# UKU207xx_power_board.net
KiCad netlist of a schematic drawn in Altium Designer
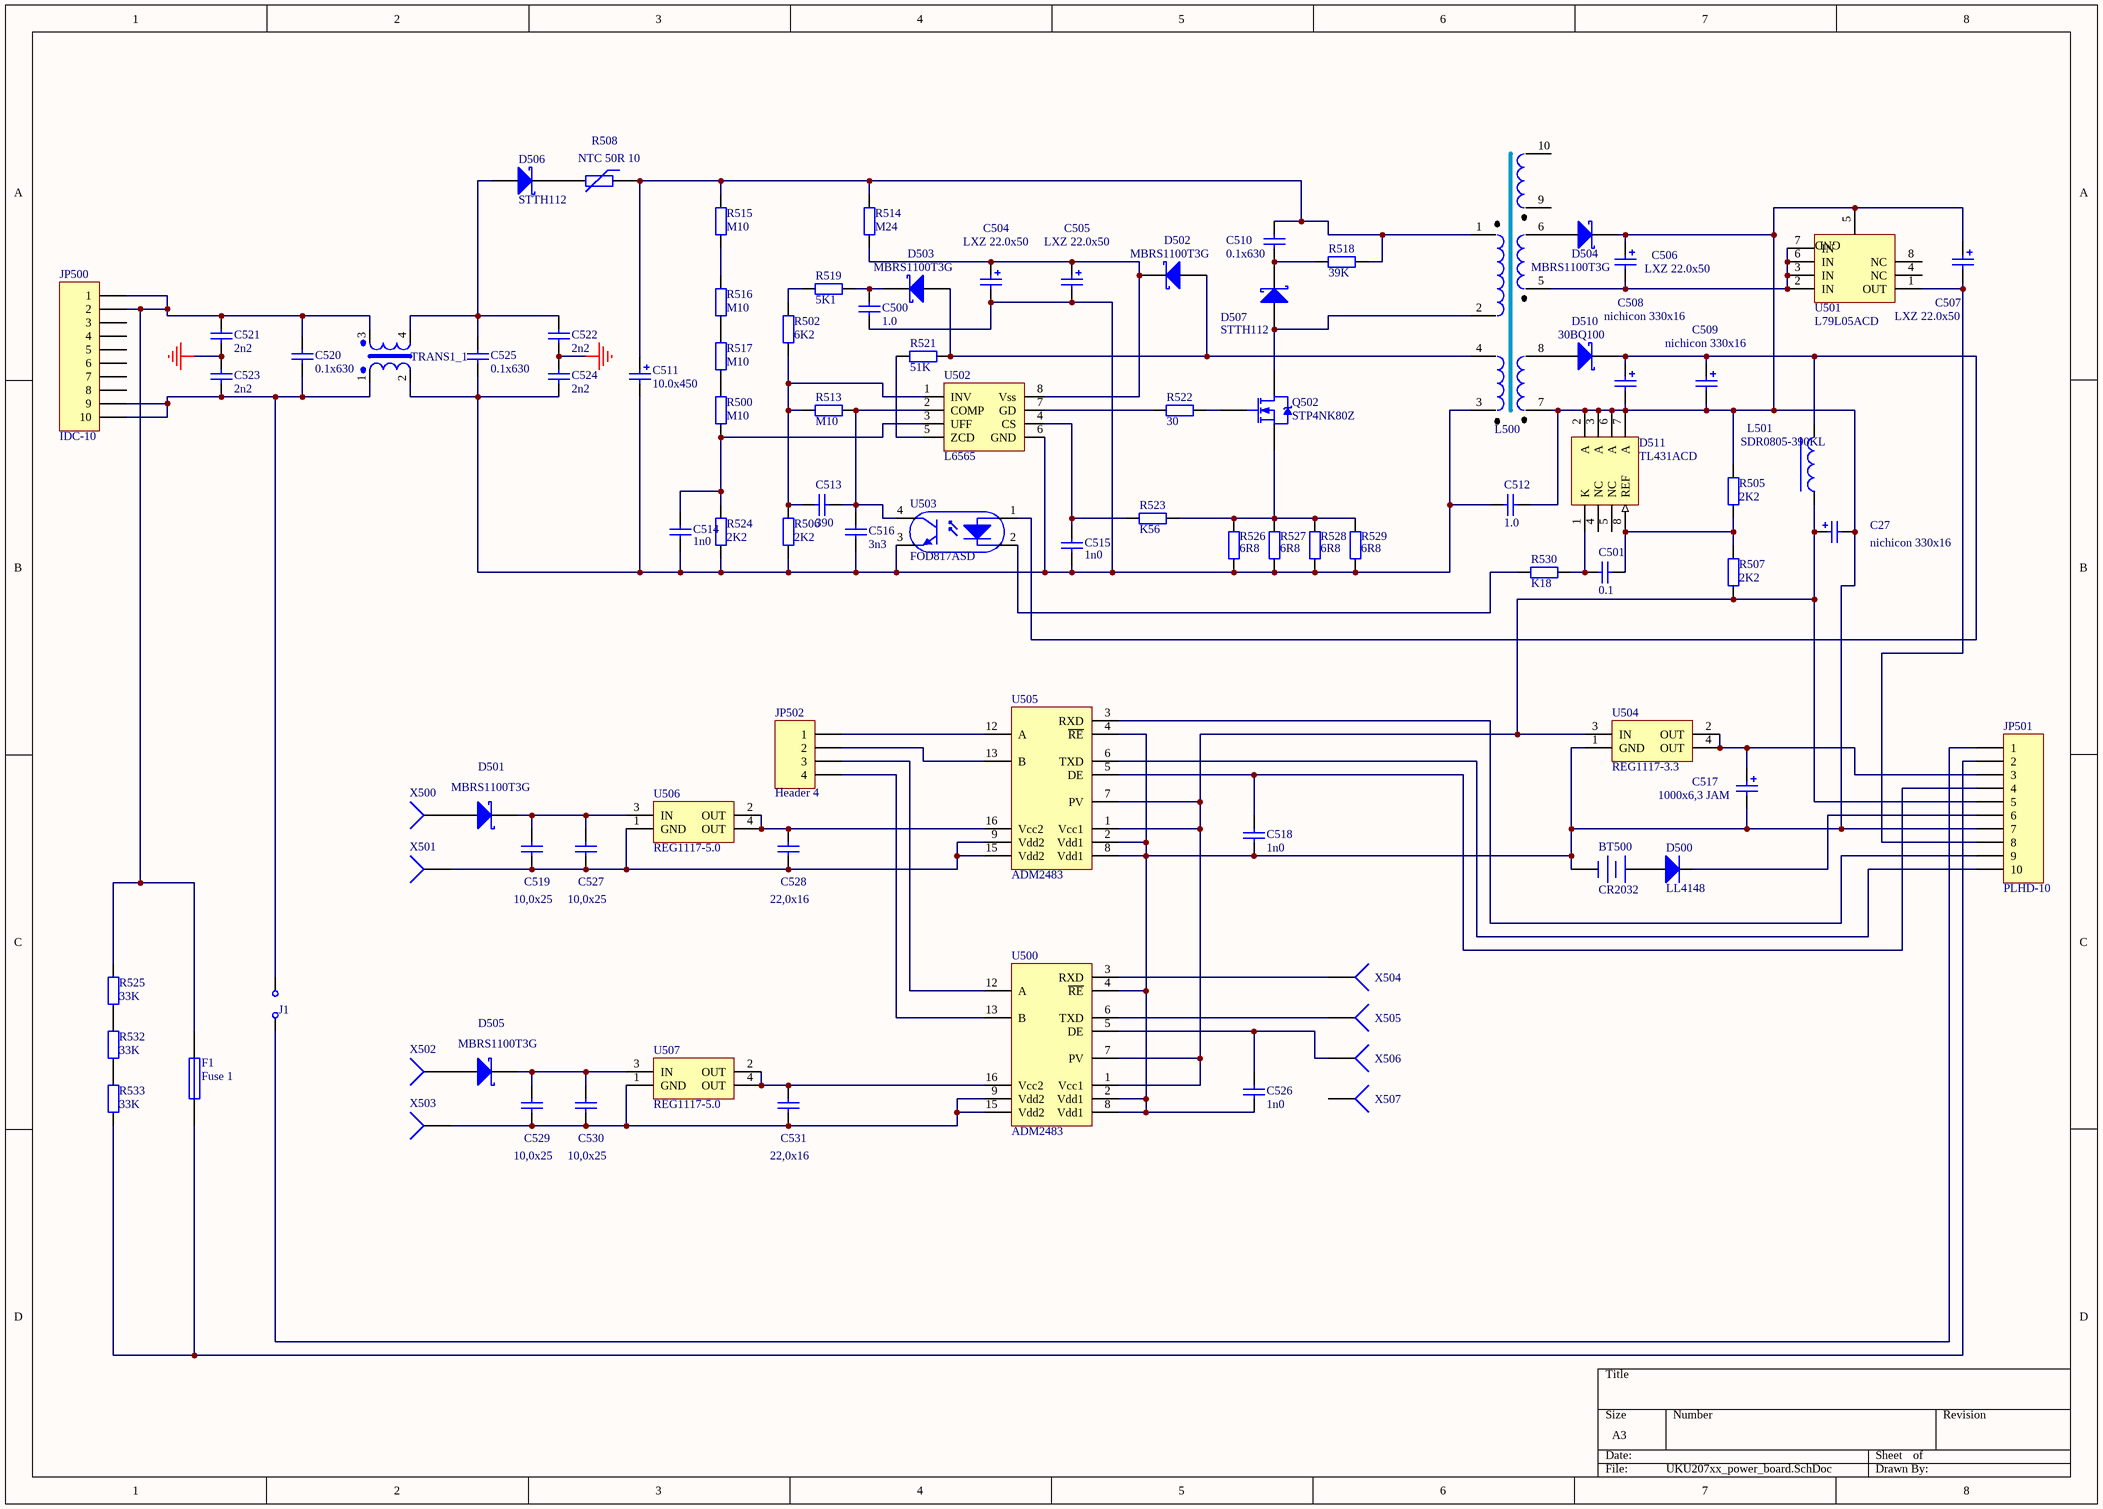
[diagram p0: UKU207xx_power_board.SchDoc]

(export (version "E")
  (design (tool "Eeschema 10.0.6"))
  (components
    (comp (ref "BT500")
      (value "CR2032")
      (footprint "BAT_HOLD_SMD")
      (description "Multicell Battery")
      (fields (field (name "MANUFACTURER") "Generic Components") (field (name "PUBLISHER") "Altium Limited"))
      (libsource (lib "Miscellaneous Devices") (part "Battery"))
    )
    (comp (ref "C27")
      (value "nichicon 330x16")
      (footprint "el3")
      (description "Polarized Capacitor (Radial)")
      (fields (field (name "MANUFACTURER") "Generic Components") (field (name "PUBLISHER") "Altium Limited"))
      (libsource (lib "PAL") (part "Cap Pol1"))
    )
    (comp (ref "C500")
      (value "1.0")
      (footprint "_1206")
      (description "Capacitor (Semiconductor SIM Model)")
      (fields (field (name "MANUFACTURER") "Generic Components") (field (name "PUBLISHER") "Altium Limited"))
      (libsource (lib "Miscellaneous Devices") (part "Cap Semi"))
    )
    (comp (ref "C501")
      (value "0.1")
      (footprint "_1206")
      (description "Capacitor (Semiconductor SIM Model)")
      (fields (field (name "MANUFACTURER") "Generic Components") (field (name "PUBLISHER") "Altium Limited"))
      (libsource (lib "Miscellaneous Devices") (part "Cap Semi"))
    )
    (comp (ref "C504")
      (value "LXZ 22.0x50")
      (footprint "el3")
      (description "Polarized Capacitor (Radial)")
      (fields (field (name "MANUFACTURER") "Generic Components") (field (name "PUBLISHER") "Altium Limited"))
      (libsource (lib "PAL") (part "Cap Pol1"))
    )
    (comp (ref "C505")
      (value "LXZ 22.0x50")
      (footprint "el3")
      (description "Polarized Capacitor (Radial)")
      (fields (field (name "MANUFACTURER") "Generic Components") (field (name "PUBLISHER") "Altium Limited"))
      (libsource (lib "PAL") (part "Cap Pol1"))
    )
    (comp (ref "C506")
      (value "LXZ 22.0x50")
      (footprint "el3")
      (description "Polarized Capacitor (Radial)")
      (fields (field (name "MANUFACTURER") "Generic Components") (field (name "PUBLISHER") "Altium Limited"))
      (libsource (lib "PAL") (part "Cap Pol1"))
    )
    (comp (ref "C507")
      (value "LXZ 22.0x50")
      (footprint "el3")
      (description "Polarized Capacitor (Radial)")
      (fields (field (name "MANUFACTURER") "Generic Components") (field (name "PUBLISHER") "Altium Limited"))
      (libsource (lib "PAL") (part "Cap Pol1"))
    )
    (comp (ref "C508")
      (value "nichicon 330x16")
      (footprint "el3")
      (description "Polarized Capacitor (Radial)")
      (fields (field (name "MANUFACTURER") "Generic Components") (field (name "PUBLISHER") "Altium Limited"))
      (libsource (lib "PAL") (part "Cap Pol1"))
    )
    (comp (ref "C509")
      (value "nichicon 330x16")
      (footprint "el3")
      (description "Polarized Capacitor (Radial)")
      (fields (field (name "MANUFACTURER") "Generic Components") (field (name "PUBLISHER") "Altium Limited"))
      (libsource (lib "PAL") (part "Cap Pol1"))
    )
    (comp (ref "C510")
      (value "0.1x630")
      (footprint "c15")
      (description "Capacitor (Semiconductor SIM Model)")
      (fields (field (name "MANUFACTURER") "Generic Components") (field (name "PUBLISHER") "Altium Limited"))
      (libsource (lib "Miscellaneous Devices") (part "Cap Semi"))
    )
    (comp (ref "C511")
      (value "10.0x450")
      (footprint "el_15_25_h")
      (description "Polarized Capacitor (Radial)")
      (fields (field (name "MANUFACTURER") "Generic Components") (field (name "PUBLISHER") "Altium Limited"))
      (libsource (lib "PAL") (part "Cap Pol1"))
    )
    (comp (ref "C512")
      (value "1.0")
      (footprint "C8")
      (description "Capacitor (Semiconductor SIM Model)")
      (fields (field (name "MANUFACTURER") "Generic Components") (field (name "PUBLISHER") "Altium Limited"))
      (libsource (lib "Miscellaneous Devices") (part "Cap Semi"))
    )
    (comp (ref "C513")
      (value "390")
      (footprint "_1206")
      (description "Capacitor (Semiconductor SIM Model)")
      (fields (field (name "MANUFACTURER") "Generic Components") (field (name "PUBLISHER") "Altium Limited"))
      (libsource (lib "Miscellaneous Devices") (part "Cap Semi"))
    )
    (comp (ref "C514")
      (value "1n0")
      (footprint "_1206")
      (description "Capacitor (Semiconductor SIM Model)")
      (fields (field (name "MANUFACTURER") "Generic Components") (field (name "PUBLISHER") "Altium Limited"))
      (libsource (lib "Miscellaneous Devices") (part "Cap Semi"))
    )
    (comp (ref "C515")
      (value "1n0")
      (footprint "_1206")
      (description "Capacitor (Semiconductor SIM Model)")
      (fields (field (name "MANUFACTURER") "Generic Components") (field (name "PUBLISHER") "Altium Limited"))
      (libsource (lib "Miscellaneous Devices") (part "Cap Semi"))
    )
    (comp (ref "C516")
      (value "3n3")
      (footprint "_1206")
      (description "Capacitor (Semiconductor SIM Model)")
      (fields (field (name "MANUFACTURER") "Generic Components") (field (name "PUBLISHER") "Altium Limited"))
      (libsource (lib "Miscellaneous Devices") (part "Cap Semi"))
    )
    (comp (ref "C517")
      (value "1000x6,3 JAM")
      (footprint "el5")
      (description "Polarized Capacitor (Radial)")
      (fields (field (name "MANUFACTURER") "Generic Components") (field (name "PUBLISHER") "Altium Limited"))
      (libsource (lib "PAL") (part "Cap Pol1"))
    )
    (comp (ref "C518")
      (value "1n0")
      (footprint "_1206")
      (description "Capacitor (Semiconductor SIM Model)")
      (fields (field (name "MANUFACTURER") "Generic Components") (field (name "PUBLISHER") "Altium Limited"))
      (libsource (lib "Miscellaneous Devices") (part "Cap Semi"))
    )
    (comp (ref "C519")
      (value "1.0")
      (footprint "_1206")
      (description "Capacitor (Semiconductor SIM Model)")
      (fields
        (field (name "MANUFACTURER") "Generic Components")
        (field (name "ALTIUM_VALUE") "10,0x25")
        (field (name "PUBLISHER") "Altium Limited")
      )
      (libsource (lib "Miscellaneous Devices") (part "Cap Semi"))
    )
    (comp (ref "C520")
      (value "0.1x630")
      (footprint "c15")
      (description "Capacitor (Semiconductor SIM Model)")
      (fields (field (name "MANUFACTURER") "Generic Components") (field (name "PUBLISHER") "Altium Limited"))
      (libsource (lib "Miscellaneous Devices") (part "Cap Semi"))
    )
    (comp (ref "C521")
      (value "2n2")
      (footprint "C8")
      (description "Capacitor (Semiconductor SIM Model)")
      (fields (field (name "MANUFACTURER") "Generic Components") (field (name "PUBLISHER") "Altium Limited"))
      (libsource (lib "Miscellaneous Devices") (part "Cap Semi"))
    )
    (comp (ref "C522")
      (value "2n2")
      (footprint "c8")
      (description "Capacitor (Semiconductor SIM Model)")
      (fields (field (name "MANUFACTURER") "Generic Components") (field (name "PUBLISHER") "Altium Limited"))
      (libsource (lib "Miscellaneous Devices") (part "Cap Semi"))
    )
    (comp (ref "C523")
      (value "2n2")
      (footprint "c8")
      (description "Capacitor (Semiconductor SIM Model)")
      (fields (field (name "MANUFACTURER") "Generic Components") (field (name "PUBLISHER") "Altium Limited"))
      (libsource (lib "Miscellaneous Devices") (part "Cap Semi"))
    )
    (comp (ref "C524")
      (value "2n2")
      (footprint "c8")
      (description "Capacitor (Semiconductor SIM Model)")
      (fields (field (name "MANUFACTURER") "Generic Components") (field (name "PUBLISHER") "Altium Limited"))
      (libsource (lib "Miscellaneous Devices") (part "Cap Semi"))
    )
    (comp (ref "C525")
      (value "0.1х630")
      (footprint "c15")
      (description "Capacitor (Semiconductor SIM Model)")
      (fields (field (name "MANUFACTURER") "Generic Components") (field (name "PUBLISHER") "Altium Limited"))
      (libsource (lib "Miscellaneous Devices") (part "Cap Semi"))
    )
    (comp (ref "C526")
      (value "1n0")
      (footprint "_1206")
      (description "Capacitor (Semiconductor SIM Model)")
      (fields (field (name "MANUFACTURER") "Generic Components") (field (name "PUBLISHER") "Altium Limited"))
      (libsource (lib "Miscellaneous Devices") (part "Cap Semi"))
    )
    (comp (ref "C527")
      (value "1.0")
      (footprint "_1206")
      (description "Capacitor (Semiconductor SIM Model)")
      (fields
        (field (name "MANUFACTURER") "Generic Components")
        (field (name "ALTIUM_VALUE") "10,0x25")
        (field (name "PUBLISHER") "Altium Limited")
      )
      (libsource (lib "Miscellaneous Devices") (part "Cap Semi"))
    )
    (comp (ref "C528")
      (value "1.0")
      (footprint "_1206")
      (description "Capacitor (Semiconductor SIM Model)")
      (fields
        (field (name "MANUFACTURER") "Generic Components")
        (field (name "ALTIUM_VALUE") "22,0x16")
        (field (name "PUBLISHER") "Altium Limited")
      )
      (libsource (lib "Miscellaneous Devices") (part "Cap Semi"))
    )
    (comp (ref "C529")
      (value "1.0")
      (footprint "_1206")
      (description "Capacitor (Semiconductor SIM Model)")
      (fields
        (field (name "MANUFACTURER") "Generic Components")
        (field (name "ALTIUM_VALUE") "10,0x25")
        (field (name "PUBLISHER") "Altium Limited")
      )
      (libsource (lib "Miscellaneous Devices") (part "Cap Semi"))
    )
    (comp (ref "C530")
      (value "1.0")
      (footprint "_1206")
      (description "Capacitor (Semiconductor SIM Model)")
      (fields
        (field (name "MANUFACTURER") "Generic Components")
        (field (name "ALTIUM_VALUE") "10,0x25")
        (field (name "PUBLISHER") "Altium Limited")
      )
      (libsource (lib "Miscellaneous Devices") (part "Cap Semi"))
    )
    (comp (ref "C531")
      (value "1.0")
      (footprint "_1206")
      (description "Capacitor (Semiconductor SIM Model)")
      (fields
        (field (name "MANUFACTURER") "Generic Components")
        (field (name "ALTIUM_VALUE") "22,0x16")
        (field (name "PUBLISHER") "Altium Limited")
      )
      (libsource (lib "Miscellaneous Devices") (part "Cap Semi"))
    )
    (comp (ref "D500")
      (value "LL4148")
      (footprint "_1206d")
      (description "Default Diode")
      (fields (field (name "MANUFACTURER") "Generic Components") (field (name "PUBLISHER") "Altium Limited"))
      (libsource (lib "PAL") (part "Diode"))
    )
    (comp (ref "D501")
      (value "MBRS1100T3G")
      (footprint "D_6_3")
      (description "Schottky Rectifier")
      (fields
        (field (name "MANUFACTURER") "International Rectifier")
        (field (name "PUBLISHER") "Altium Limited")
      )
      (libsource (lib "IR Discrete Diode") (part "10BQ015"))
    )
    (comp (ref "D502")
      (value "MBRS1100T3G")
      (footprint "D_6_3")
      (description "Schottky Rectifier")
      (fields
        (field (name "MANUFACTURER") "International Rectifier")
        (field (name "PUBLISHER") "Altium Limited")
      )
      (libsource (lib "IR Discrete Diode") (part "10BQ015"))
    )
    (comp (ref "D503")
      (value "MBRS1100T3G")
      (footprint "D_6_3")
      (description "Schottky Rectifier")
      (fields
        (field (name "MANUFACTURER") "International Rectifier")
        (field (name "PUBLISHER") "Altium Limited")
      )
      (libsource (lib "IR Discrete Diode") (part "10BQ015"))
    )
    (comp (ref "D504")
      (value "MBRS1100T3G")
      (footprint "D_6_3")
      (description "Schottky Rectifier")
      (fields
        (field (name "MANUFACTURER") "International Rectifier")
        (field (name "PUBLISHER") "Altium Limited")
      )
      (libsource (lib "IR Discrete Diode") (part "10BQ015"))
    )
    (comp (ref "D505")
      (value "MBRS1100T3G")
      (footprint "D_6_3")
      (description "Schottky Rectifier")
      (fields
        (field (name "MANUFACTURER") "International Rectifier")
        (field (name "PUBLISHER") "Altium Limited")
      )
      (libsource (lib "IR Discrete Diode") (part "10BQ015"))
    )
    (comp (ref "D506")
      (value "STTH112")
      (footprint "D_6_3")
      (description "Schottky Diode")
      (fields
        (field (name "MANUFACTURER") "International Rectifier")
        (field (name "PUBLISHER") "Altium Limited")
      )
      (libsource (lib "IR Discrete Diode") (part "10BQ015"))
    )
    (comp (ref "D507")
      (value "STTH112")
      (footprint "D_6_3")
      (description "Schottky Diode")
      (fields
        (field (name "MANUFACTURER") "International Rectifier")
        (field (name "PUBLISHER") "Altium Limited")
      )
      (libsource (lib "IR Discrete Diode") (part "10BQ015"))
    )
    (comp (ref "D510")
      (value "30BQ100")
      (footprint "30BQ100")
      (description "Schottky Rectifier")
      (fields
        (field (name "MANUFACTURER") "International Rectifier")
        (field (name "PUBLISHER") "Altium Limited")
      )
      (libsource (lib "IR Discrete Diode") (part "10BQ015"))
    )
    (comp (ref "D511")
      (value "TL431ACD")
      (footprint "SO-G8")
      (description "Programmable Precision Reference")
      (fields (field (name "MANUFACTURER") "Motorola") (field (name "PUBLISHER") "Altium Limited"))
      (libsource (lib "Motorola Power Management Voltage Reference") (part "TL431ACD"))
    )
    (comp (ref "F1")
      (value "Fuse 1")
      (footprint "PIN-W2/E2.8")
      (description "Fuse")
      (fields (field (name "MANUFACTURER") "Generic Components") (field (name "PUBLISHER") "Altium Limited"))
      (libsource (lib "Miscellaneous Devices") (part "Fuse 1"))
    )
    (comp (ref "J1")
      (value "~")
      (footprint "BT5-2")
      (description "Switch")
      (fields (field (name "MANUFACTURER") "Generic Components") (field (name "PUBLISHER") "Altium Limited"))
      (libsource (lib "PAL") (part "JMP"))
    )
    (comp (ref "JP500")
      (value "IDC-10")
      (footprint "HDR2X5")
      (description "Header, 10-Pin")
      (fields (field (name "MANUFACTURER") "Generic Components") (field (name "PUBLISHER") "Altium Limited"))
      (libsource (lib "") (part "Header 10_1"))
    )
    (comp (ref "JP501")
      (value "PLHD-10")
      (footprint "HDR2X5")
      (description "Header, 10-Pin")
      (fields (field (name "MANUFACTURER") "Generic Components") (field (name "PUBLISHER") "Altium Limited"))
      (libsource (lib "Miscellaneous Connectors") (part "Header 10"))
    )
    (comp (ref "JP502")
      (value "Header 4")
      (footprint "PAL:2EDG-5.08-4")
      (description "Header, 4-Pin")
      (fields (field (name "MANUFACTURER") "Generic Components") (field (name "PUBLISHER") "Altium Limited"))
      (libsource (lib "Miscellaneous Connectors") (part "Header 4"))
    )
    (comp (ref "L500")
      (value "L220-K10")
      (footprint "trans_ring1")
      (description "Дроссель")
      (libsource (lib "PAL") (part "L1_dc_2"))
    )
    (comp (ref "L501")
      (value "SDR0805-390KL")
      (footprint "L10x10")
      (description "Magnetic-Core Inductor")
      (fields (field (name "MANUFACTURER") "Generic Components") (field (name "PUBLISHER") "Altium Limited"))
      (libsource (lib "PAL") (part "Inductor Konstr 2"))
    )
    (comp (ref "Q502")
      (value "STP4NK80Z")
      (footprint "TO220_h")
      (description "N-Channel Power MOSFET")
      (fields (field (name "MANUFACTURER") "Generic Components") (field (name "PUBLISHER") "Altium Limited"))
      (libsource (lib "Miscellaneous Devices") (part "NMOS-2"))
    )
    (comp (ref "R500")
      (value "M10")
      (footprint "_1206")
      (description "Resistor")
      (fields (field (name "MANUFACTURER") "Generic Components") (field (name "PUBLISHER") "Altium Limited"))
      (libsource (lib "") (part "Res2_2"))
    )
    (comp (ref "R502")
      (value "6K2")
      (footprint "_1206")
      (description "Resistor")
      (fields (field (name "MANUFACTURER") "Generic Components") (field (name "PUBLISHER") "Altium Limited"))
      (libsource (lib "") (part "Res2_2"))
    )
    (comp (ref "R505")
      (value "2K2")
      (footprint "_1206")
      (description "Resistor")
      (fields (field (name "MANUFACTURER") "Generic Components") (field (name "PUBLISHER") "Altium Limited"))
      (libsource (lib "") (part "Res2_2"))
    )
    (comp (ref "R506")
      (value "2K2")
      (footprint "_1206")
      (description "Resistor")
      (fields (field (name "MANUFACTURER") "Generic Components") (field (name "PUBLISHER") "Altium Limited"))
      (libsource (lib "") (part "Res2_2"))
    )
    (comp (ref "R507")
      (value "2K2")
      (footprint "_1206")
      (description "Resistor")
      (fields (field (name "MANUFACTURER") "Generic Components") (field (name "PUBLISHER") "Altium Limited"))
      (libsource (lib "") (part "Res2_2"))
    )
    (comp (ref "R508")
      (value "NTC 50R 10")
      (footprint "JVR07N")
      (description "Varistor (Voltage-Sensitive Resistor)")
      (fields (field (name "MANUFACTURER") "Generic Components") (field (name "PUBLISHER") "Altium Limited"))
      (libsource (lib "Miscellaneous Devices") (part "Res Varistor"))
    )
    (comp (ref "R513")
      (value "M10")
      (footprint "_1206")
      (description "Resistor")
      (fields (field (name "MANUFACTURER") "Generic Components") (field (name "PUBLISHER") "Altium Limited"))
      (libsource (lib "Miscellaneous Devices") (part "Res2"))
    )
    (comp (ref "R514")
      (value "M24")
      (footprint "AXIAL-0.7")
      (description "Resistor")
      (fields (field (name "MANUFACTURER") "Generic Components") (field (name "PUBLISHER") "Altium Limited"))
      (libsource (lib "") (part "Res2_2"))
    )
    (comp (ref "R515")
      (value "M10")
      (footprint "_1206")
      (description "Resistor")
      (fields (field (name "MANUFACTURER") "Generic Components") (field (name "PUBLISHER") "Altium Limited"))
      (libsource (lib "") (part "Res2_2"))
    )
    (comp (ref "R516")
      (value "M10")
      (footprint "_1206")
      (description "Resistor")
      (fields (field (name "MANUFACTURER") "Generic Components") (field (name "PUBLISHER") "Altium Limited"))
      (libsource (lib "") (part "Res2_2"))
    )
    (comp (ref "R517")
      (value "M10")
      (footprint "_1206")
      (description "Resistor")
      (fields (field (name "MANUFACTURER") "Generic Components") (field (name "PUBLISHER") "Altium Limited"))
      (libsource (lib "") (part "Res2_2"))
    )
    (comp (ref "R518")
      (value "39K")
      (footprint "AXIAL-0.7")
      (description "Resistor")
      (fields (field (name "MANUFACTURER") "Generic Components") (field (name "PUBLISHER") "Altium Limited"))
      (libsource (lib "Miscellaneous Devices") (part "Res2"))
    )
    (comp (ref "R519")
      (value "5K1")
      (footprint "_1206")
      (description "Resistor")
      (fields (field (name "MANUFACTURER") "Generic Components") (field (name "PUBLISHER") "Altium Limited"))
      (libsource (lib "Miscellaneous Devices") (part "Res2"))
    )
    (comp (ref "R521")
      (value "51K")
      (footprint "_1206")
      (description "Resistor")
      (fields (field (name "MANUFACTURER") "Generic Components") (field (name "PUBLISHER") "Altium Limited"))
      (libsource (lib "Miscellaneous Devices") (part "Res2"))
    )
    (comp (ref "R522")
      (value "30")
      (footprint "_1206")
      (description "Resistor")
      (fields (field (name "MANUFACTURER") "Generic Components") (field (name "PUBLISHER") "Altium Limited"))
      (libsource (lib "Miscellaneous Devices") (part "Res2"))
    )
    (comp (ref "R523")
      (value "K56")
      (footprint "_1206")
      (description "Resistor")
      (fields (field (name "MANUFACTURER") "Generic Components") (field (name "PUBLISHER") "Altium Limited"))
      (libsource (lib "Miscellaneous Devices") (part "Res2"))
    )
    (comp (ref "R524")
      (value "2K2")
      (footprint "_1206")
      (description "Resistor")
      (fields (field (name "MANUFACTURER") "Generic Components") (field (name "PUBLISHER") "Altium Limited"))
      (libsource (lib "") (part "Res2_2"))
    )
    (comp (ref "R525")
      (value "33K")
      (footprint "_1206")
      (description "Resistor")
      (fields (field (name "MANUFACTURER") "Generic Components") (field (name "PUBLISHER") "Altium Limited"))
      (libsource (lib "") (part "Res2_2"))
    )
    (comp (ref "R526")
      (value "6R8")
      (footprint "_1206")
      (description "Resistor")
      (fields (field (name "MANUFACTURER") "Generic Components") (field (name "PUBLISHER") "Altium Limited"))
      (libsource (lib "") (part "Res2_1"))
    )
    (comp (ref "R527")
      (value "6R8")
      (footprint "_1206")
      (description "Resistor")
      (fields (field (name "MANUFACTURER") "Generic Components") (field (name "PUBLISHER") "Altium Limited"))
      (libsource (lib "") (part "Res2_1"))
    )
    (comp (ref "R528")
      (value "6R8")
      (footprint "_1206")
      (description "Resistor")
      (fields (field (name "MANUFACTURER") "Generic Components") (field (name "PUBLISHER") "Altium Limited"))
      (libsource (lib "") (part "Res2_1"))
    )
    (comp (ref "R529")
      (value "6R8")
      (footprint "_1206")
      (description "Resistor")
      (fields (field (name "MANUFACTURER") "Generic Components") (field (name "PUBLISHER") "Altium Limited"))
      (libsource (lib "") (part "Res2_1"))
    )
    (comp (ref "R530")
      (value "K18")
      (footprint "_1206")
      (description "Resistor")
      (fields (field (name "MANUFACTURER") "Generic Components") (field (name "PUBLISHER") "Altium Limited"))
      (libsource (lib "Miscellaneous Devices") (part "Res2"))
    )
    (comp (ref "R532")
      (value "33K")
      (footprint "_1206")
      (description "Resistor")
      (fields (field (name "MANUFACTURER") "Generic Components") (field (name "PUBLISHER") "Altium Limited"))
      (libsource (lib "") (part "Res2_2"))
    )
    (comp (ref "R533")
      (value "33K")
      (footprint "_1206")
      (description "Resistor")
      (fields (field (name "MANUFACTURER") "Generic Components") (field (name "PUBLISHER") "Altium Limited"))
      (libsource (lib "") (part "Res2_2"))
    )
    (comp (ref "T500")
      (value "TRANS1_1")
      (footprint "3030R4")
      (fields (field (name "MANUFACTURER") "Generic Components") (field (name "PUBLISHER") "Altium Limited"))
      (libsource (lib "PAL") (part "TRANS1_1"))
    )
    (comp (ref "U500") (value "ADM2483") (footprint "SO-G16/D10.4") (libsource (lib "PAL") (part "ADM2483")))
    (comp (ref "U501")
      (value "L79L05ACD")
      (footprint "SO-G8")
      (description "Negative Voltage Regulator")
      (fields (field (name "MANUFACTURER") "ST-Microelectronics") (field (name "PUBLISHER") "Altium Limited"))
      (libsource (lib "ST Power Mgt Voltage Regulator") (part "L79L05ACD"))
    )
    (comp (ref "U502") (value "L6565") (footprint "so-g8") (libsource (lib "PAL") (part "L6565")))
    (comp (ref "U503") (value "FOD817ASD") (footprint "FOD817ASD") (libsource (lib "PAL") (part "F00817ASD")))
    (comp (ref "U504")
      (value "REG1117-3.3")
      (footprint "DSO-G3")
      (description "800mA and 1A Low Dropout Positive Regulator 2.85V, 3.3V, 5V, and Adjustable")
      (fields (field (name "MANUFACTURER") "Burr-Brown") (field (name "PUBLISHER") "Altium Limited"))
      (libsource (lib "BB Power Mgt Voltage Regulator") (part "REG1117-3.3"))
    )
    (comp (ref "U505") (value "ADM2483") (footprint "SO-G16/D10.4") (libsource (lib "PAL") (part "ADM2483")))
    (comp (ref "U506")
      (value "REG1117-5.0")
      (footprint "DSO-G3")
      (description "800mA and 1A Low Dropout Positive Regulator 2.85V, 3.3V, 5V, and Adjustable")
      (fields (field (name "MANUFACTURER") "Burr-Brown") (field (name "PUBLISHER") "Altium Limited"))
      (libsource (lib "BB Power Mgt Voltage Regulator") (part "REG1117-3.3"))
    )
    (comp (ref "U507")
      (value "REG1117-5.0")
      (footprint "DSO-G3")
      (description "800mA and 1A Low Dropout Positive Regulator 2.85V, 3.3V, 5V, and Adjustable")
      (fields (field (name "MANUFACTURER") "Burr-Brown") (field (name "PUBLISHER") "Altium Limited"))
      (libsource (lib "BB Power Mgt Voltage Regulator") (part "REG1117-3.3"))
    )
    (comp (ref "X500")
      (value "Socket")
      (footprint "PIN1")
      (fields (field (name "MANUFACTURER") "Generic Components") (field (name "PUBLISHER") "Altium Limited"))
      (libsource (lib "Miscellaneous Connectors") (part "Socket"))
    )
    (comp (ref "X501")
      (value "Socket")
      (footprint "PIN1")
      (fields (field (name "MANUFACTURER") "Generic Components") (field (name "PUBLISHER") "Altium Limited"))
      (libsource (lib "Miscellaneous Connectors") (part "Socket"))
    )
    (comp (ref "X502")
      (value "Socket")
      (footprint "PIN1")
      (fields (field (name "MANUFACTURER") "Generic Components") (field (name "PUBLISHER") "Altium Limited"))
      (libsource (lib "Miscellaneous Connectors") (part "Socket"))
    )
    (comp (ref "X503")
      (value "Socket")
      (footprint "PIN1")
      (fields (field (name "MANUFACTURER") "Generic Components") (field (name "PUBLISHER") "Altium Limited"))
      (libsource (lib "Miscellaneous Connectors") (part "Socket"))
    )
    (comp (ref "X504")
      (value "Socket")
      (footprint "PIN1")
      (fields (field (name "MANUFACTURER") "Generic Components") (field (name "PUBLISHER") "Altium Limited"))
      (libsource (lib "Miscellaneous Connectors") (part "Socket"))
    )
    (comp (ref "X505")
      (value "Socket")
      (footprint "PIN1")
      (fields (field (name "MANUFACTURER") "Generic Components") (field (name "PUBLISHER") "Altium Limited"))
      (libsource (lib "Miscellaneous Connectors") (part "Socket"))
    )
    (comp (ref "X506")
      (value "Socket")
      (footprint "PIN1")
      (fields (field (name "MANUFACTURER") "Generic Components") (field (name "PUBLISHER") "Altium Limited"))
      (libsource (lib "Miscellaneous Connectors") (part "Socket"))
    )
    (comp (ref "X507")
      (value "Socket")
      (footprint "PIN1")
      (fields (field (name "MANUFACTURER") "Generic Components") (field (name "PUBLISHER") "Altium Limited"))
      (libsource (lib "Miscellaneous Connectors") (part "Socket"))
    )
  )
  (nets
    (net (code "1") (name "GND_GND") (class "Default")
      (node (ref "C521") (pin "1") (pinfunction "1_1") (pintype "passive"))
      (node (ref "C522") (pin "1") (pinfunction "1_1") (pintype "passive"))
      (node (ref "C523") (pin "2") (pinfunction "2_2") (pintype "passive"))
      (node (ref "C524") (pin "2") (pinfunction "2_2") (pintype "passive"))
    )
    (net (code "2") (name "Net-(BT500-+)") (class "Default")
      (node (ref "BT500") (pin "1") (pinfunction "+_1") (pintype "passive"))
      (node (ref "D500") (pin "1") (pinfunction "A_1") (pintype "passive"))
    )
    (net (code "3") (name "Net-(BT500--)") (class "Default")
      (node (ref "BT500") (pin "2") (pinfunction "-_2") (pintype "passive"))
      (node (ref "C27") (pin "2") (pinfunction "2_2") (pintype "passive"))
      (node (ref "C506") (pin "1") (pinfunction "1_1") (pintype "passive"))
      (node (ref "C507") (pin "1") (pinfunction "1_1") (pintype "passive"))
      (node (ref "C508") (pin "2") (pinfunction "2_2") (pintype "passive"))
      (node (ref "C509") (pin "2") (pinfunction "2_2") (pintype "passive"))
      (node (ref "C512") (pin "1") (pinfunction "1_1") (pintype "passive"))
      (node (ref "C517") (pin "2") (pinfunction "2_2") (pintype "passive"))
      (node (ref "C518") (pin "1") (pinfunction "1_1") (pintype "passive"))
      (node (ref "C526") (pin "1") (pinfunction "1_1") (pintype "passive"))
      (node (ref "D504") (pin "2") (pinfunction "K_2") (pintype "passive"))
      (node (ref "D511") (pin "2") (pinfunction "A_2") (pintype "passive"))
      (node (ref "D511") (pin "3") (pinfunction "A_3") (pintype "passive"))
      (node (ref "D511") (pin "6") (pinfunction "A_6") (pintype "passive"))
      (node (ref "D511") (pin "7") (pinfunction "A_7") (pintype "passive"))
      (node (ref "JP501") (pin "7") (pinfunction "7_7") (pintype "passive"))
      (node (ref "L500") (pin "7") (pintype "passive"))
      (node (ref "R505") (pin "2") (pinfunction "2_2") (pintype "passive"))
      (node (ref "U500") (pin "2") (pinfunction "Vdd1_2") (pintype "passive"))
      (node (ref "U500") (pin "4") (pinfunction "~{RE}_4") (pintype "passive"))
      (node (ref "U500") (pin "8") (pinfunction "Vdd1_8") (pintype "passive"))
      (node (ref "U501") (pin "5") (pinfunction "GND_5") (pintype "power_in"))
      (node (ref "U504") (pin "1") (pinfunction "GND_1") (pintype "power_in"))
      (node (ref "U505") (pin "2") (pinfunction "Vdd1_2") (pintype "passive"))
      (node (ref "U505") (pin "4") (pinfunction "~{RE}_4") (pintype "passive"))
      (node (ref "U505") (pin "8") (pinfunction "Vdd1_8") (pintype "passive"))
    )
    (net (code "4") (name "Net-(C506-Pad2)") (class "Default")
      (node (ref "C506") (pin "2") (pinfunction "2_2") (pintype "passive"))
      (node (ref "L500") (pin "5") (pintype "passive"))
      (node (ref "U501") (pin "2") (pinfunction "IN_2") (pintype "power_in"))
      (node (ref "U501") (pin "3") (pinfunction "IN_3") (pintype "power_in"))
      (node (ref "U501") (pin "6") (pinfunction "IN_6") (pintype "power_in"))
      (node (ref "U501") (pin "7") (pinfunction "IN_7") (pintype "power_in"))
    )
    (net (code "5") (name "Net-(C510-Pad2)") (class "Default")
      (node (ref "C510") (pin "2") (pinfunction "2_2") (pintype "passive"))
      (node (ref "C511") (pin "1") (pinfunction "1_1") (pintype "passive"))
      (node (ref "L500") (pin "1") (pintype "passive"))
      (node (ref "R508") (pin "1") (pinfunction "1_1") (pintype "passive"))
      (node (ref "R514") (pin "2") (pinfunction "2_2") (pintype "passive"))
      (node (ref "R515") (pin "2") (pinfunction "2_2") (pintype "passive"))
      (node (ref "R518") (pin "1") (pinfunction "1_1") (pintype "passive"))
    )
    (net (code "6") (name "Net-(C517-Pad1)") (class "Default")
      (node (ref "C517") (pin "1") (pinfunction "1_1") (pintype "passive"))
      (node (ref "JP501") (pin "3") (pinfunction "3_3") (pintype "passive"))
      (node (ref "U504") (pin "2") (pinfunction "OUT_2") (pintype "power_in"))
      (node (ref "U504") (pin "4") (pinfunction "OUT_4") (pintype "power_in"))
    )
    (net (code "7") (name "Net-(D500-K)") (class "Default")
      (node (ref "D500") (pin "2") (pinfunction "K_2") (pintype "passive"))
      (node (ref "JP501") (pin "6") (pinfunction "6_6") (pintype "passive"))
    )
    (net (code "8") (name "Net-(D501-A)") (class "Default")
      (node (ref "D501") (pin "1") (pinfunction "A_1") (pintype "passive"))
      (node (ref "X500") (pin "1") (pinfunction "1_1") (pintype "passive"))
    )
    (net (code "9") (name "Net-(D501-K)") (class "Default")
      (node (ref "C519") (pin "2") (pinfunction "2_2") (pintype "passive"))
      (node (ref "C527") (pin "2") (pinfunction "2_2") (pintype "passive"))
      (node (ref "D501") (pin "2") (pinfunction "K_2") (pintype "passive"))
      (node (ref "U506") (pin "3") (pinfunction "IN_3") (pintype "power_in"))
    )
    (net (code "10") (name "Net-(D502-A)") (class "Default")
      (node (ref "D502") (pin "1") (pinfunction "A_1") (pintype "passive"))
      (node (ref "D503") (pin "1") (pinfunction "A_1") (pintype "passive"))
      (node (ref "L500") (pin "4") (pintype "passive"))
      (node (ref "R521") (pin "1") (pinfunction "1_1") (pintype "passive"))
    )
    (net (code "11") (name "Net-(D502-K)") (class "Default")
      (node (ref "C504") (pin "1") (pinfunction "1_1") (pintype "passive"))
      (node (ref "C505") (pin "1") (pinfunction "1_1") (pintype "passive"))
      (node (ref "D502") (pin "2") (pinfunction "K_2") (pintype "passive"))
      (node (ref "R514") (pin "1") (pinfunction "1_1") (pintype "passive"))
      (node (ref "U502") (pin "8") (pinfunction "Vss_8") (pintype "passive"))
    )
    (net (code "12") (name "Net-(D503-K)") (class "Default")
      (node (ref "C500") (pin "2") (pinfunction "2_2") (pintype "passive"))
      (node (ref "D503") (pin "2") (pinfunction "K_2") (pintype "passive"))
      (node (ref "R519") (pin "1") (pinfunction "1_1") (pintype "passive"))
    )
    (net (code "13") (name "Net-(D504-A)") (class "Default")
      (node (ref "D504") (pin "1") (pinfunction "A_1") (pintype "passive"))
      (node (ref "L500") (pin "6") (pintype "passive"))
    )
    (net (code "14") (name "Net-(D505-A)") (class "Default")
      (node (ref "D505") (pin "1") (pinfunction "A_1") (pintype "passive"))
      (node (ref "X502") (pin "1") (pinfunction "1_1") (pintype "passive"))
    )
    (net (code "15") (name "Net-(D505-K)") (class "Default")
      (node (ref "C529") (pin "2") (pinfunction "2_2") (pintype "passive"))
      (node (ref "C530") (pin "2") (pinfunction "2_2") (pintype "passive"))
      (node (ref "D505") (pin "2") (pinfunction "K_2") (pintype "passive"))
      (node (ref "U507") (pin "3") (pinfunction "IN_3") (pintype "power_in"))
    )
    (net (code "16") (name "Net-(D506-A)") (class "Default")
      (node (ref "C522") (pin "2") (pinfunction "2_2") (pintype "passive"))
      (node (ref "C525") (pin "2") (pinfunction "2_2") (pintype "passive"))
      (node (ref "D506") (pin "1") (pinfunction "A_1") (pintype "passive"))
      (node (ref "T500") (pin "4") (pinfunction "Sec1-_4") (pintype "passive"))
    )
    (net (code "17") (name "Net-(D506-K)") (class "Default")
      (node (ref "D506") (pin "2") (pinfunction "K_2") (pintype "passive"))
      (node (ref "R508") (pin "2") (pinfunction "2_2") (pintype "passive"))
    )
    (net (code "18") (name "Net-(D507-A)") (class "Default")
      (node (ref "D507") (pin "1") (pinfunction "A_1") (pintype "passive"))
      (node (ref "L500") (pin "2") (pintype "passive"))
      (node (ref "Q502") (pin "2") (pinfunction "D_2") (pintype "passive"))
    )
    (net (code "19") (name "Net-(D507-K)") (class "Default")
      (node (ref "C510") (pin "1") (pinfunction "1_1") (pintype "passive"))
      (node (ref "D507") (pin "2") (pinfunction "K_2") (pintype "passive"))
      (node (ref "R518") (pin "2") (pinfunction "2_2") (pintype "passive"))
    )
    (net (code "20") (name "Net-(D510-A)") (class "Default")
      (node (ref "D510") (pin "1") (pinfunction "A_1") (pintype "passive"))
      (node (ref "L500") (pin "8") (pintype "passive"))
    )
    (net (code "21") (name "Net-(D510-K)") (class "Default")
      (node (ref "C508") (pin "1") (pinfunction "1_1") (pintype "passive"))
      (node (ref "C509") (pin "1") (pinfunction "1_1") (pintype "passive"))
      (node (ref "D510") (pin "2") (pinfunction "K_2") (pintype "passive"))
      (node (ref "L501") (pin "2") (pinfunction "2_2") (pintype "passive"))
      (node (ref "U503") (pin "1") (pinfunction "0_1") (pintype "passive"))
    )
    (net (code "22") (name "Net-(D511-K)") (class "Default")
      (node (ref "C501") (pin "2") (pinfunction "2_2") (pintype "passive"))
      (node (ref "D511") (pin "1") (pinfunction "K_1") (pintype "passive"))
      (node (ref "R530") (pin "1") (pinfunction "1_1") (pintype "passive"))
    )
    (net (code "23") (name "Net-(D511-REF)") (class "Default")
      (node (ref "C501") (pin "1") (pinfunction "1_1") (pintype "passive"))
      (node (ref "D511") (pin "8") (pinfunction "REF_8") (pintype "input"))
      (node (ref "R505") (pin "1") (pinfunction "1_1") (pintype "passive"))
      (node (ref "R507") (pin "2") (pinfunction "2_2") (pintype "passive"))
    )
    (net (code "24") (name "Net-(F1-Pad1)") (class "Default")
      (node (ref "F1") (pin "1") (pinfunction "1_1") (pintype "passive"))
      (node (ref "JP501") (pin "2") (pinfunction "2_2") (pintype "passive"))
      (node (ref "R533") (pin "1") (pinfunction "1_1") (pintype "passive"))
    )
    (net (code "25") (name "Net-(J1-Pad2)") (class "Default")
      (node (ref "J1") (pin "2") (pinfunction "2_2") (pintype "passive"))
      (node (ref "JP501") (pin "1") (pinfunction "1_1") (pintype "passive"))
    )
    (net (code "26") (name "Net-(Q502-G)") (class "Default")
      (node (ref "Q502") (pin "1") (pinfunction "G_1") (pintype "passive"))
      (node (ref "R522") (pin "1") (pinfunction "1_1") (pintype "passive"))
    )
    (net (code "27") (name "Net-(Q502-S)") (class "Default")
      (node (ref "Q502") (pin "3") (pinfunction "S_3") (pintype "passive"))
      (node (ref "R523") (pin "1") (pinfunction "1_1") (pintype "passive"))
      (node (ref "R526") (pin "1") (pinfunction "1_1") (pintype "passive"))
      (node (ref "R527") (pin "1") (pinfunction "1_1") (pintype "passive"))
      (node (ref "R528") (pin "1") (pinfunction "1_1") (pintype "passive"))
      (node (ref "R529") (pin "1") (pinfunction "1_1") (pintype "passive"))
    )
    (net (code "28") (name "Net-(R500-Pad2)") (class "Default")
      (node (ref "R500") (pin "2") (pinfunction "2_2") (pintype "passive"))
      (node (ref "R517") (pin "1") (pinfunction "1_1") (pintype "passive"))
    )
    (net (code "29") (name "Net-(R502-Pad2)") (class "Default")
      (node (ref "R502") (pin "2") (pinfunction "2_2") (pintype "passive"))
      (node (ref "R519") (pin "2") (pinfunction "2_2") (pintype "passive"))
    )
    (net (code "30") (name "Net-(R515-Pad1)") (class "Default")
      (node (ref "R515") (pin "1") (pinfunction "1_1") (pintype "passive"))
      (node (ref "R516") (pin "2") (pinfunction "2_2") (pintype "passive"))
    )
    (net (code "31") (name "Net-(R516-Pad1)") (class "Default")
      (node (ref "R516") (pin "1") (pinfunction "1_1") (pintype "passive"))
      (node (ref "R517") (pin "2") (pinfunction "2_2") (pintype "passive"))
    )
    (net (code "32") (name "Net-(R525-Pad1)") (class "Default")
      (node (ref "R525") (pin "1") (pinfunction "1_1") (pintype "passive"))
      (node (ref "R532") (pin "2") (pinfunction "2_2") (pintype "passive"))
    )
    (net (code "33") (name "Net-(R532-Pad1)") (class "Default")
      (node (ref "R532") (pin "1") (pinfunction "1_1") (pintype "passive"))
      (node (ref "R533") (pin "2") (pinfunction "2_2") (pintype "passive"))
    )
    (net (code "34") (name "Net-(T500-Pri+)") (class "Default")
      (node (ref "C520") (pin "1") (pinfunction "1_1") (pintype "passive"))
      (node (ref "C523") (pin "1") (pinfunction "1_1") (pintype "passive"))
      (node (ref "J1") (pin "1") (pinfunction "1_1") (pintype "passive"))
      (node (ref "JP500") (pin "10") (pinfunction "10_10") (pintype "passive"))
      (node (ref "JP500") (pin "9") (pinfunction "9_9") (pintype "passive"))
      (node (ref "T500") (pin "1") (pinfunction "Pri+_1") (pintype "passive"))
    )
    (net (code "35") (name "Net-(T500-Pri-)") (class "Default")
      (node (ref "C500") (pin "1") (pinfunction "1_1") (pintype "passive"))
      (node (ref "C504") (pin "2") (pinfunction "2_2") (pintype "passive"))
      (node (ref "C505") (pin "2") (pinfunction "2_2") (pintype "passive"))
      (node (ref "C511") (pin "2") (pinfunction "2_2") (pintype "passive"))
      (node (ref "C512") (pin "2") (pinfunction "2_2") (pintype "passive"))
      (node (ref "C514") (pin "2") (pinfunction "2_2") (pintype "passive"))
      (node (ref "C515") (pin "2") (pinfunction "2_2") (pintype "passive"))
      (node (ref "C516") (pin "1") (pinfunction "1_1") (pintype "passive"))
      (node (ref "C524") (pin "1") (pinfunction "1_1") (pintype "passive"))
      (node (ref "C525") (pin "1") (pinfunction "1_1") (pintype "passive"))
      (node (ref "L500") (pin "3") (pintype "passive"))
      (node (ref "R506") (pin "1") (pinfunction "1_1") (pintype "passive"))
      (node (ref "R524") (pin "1") (pinfunction "1_1") (pintype "passive"))
      (node (ref "R526") (pin "2") (pinfunction "2_2") (pintype "passive"))
      (node (ref "R527") (pin "2") (pinfunction "2_2") (pintype "passive"))
      (node (ref "R528") (pin "2") (pinfunction "2_2") (pintype "passive"))
      (node (ref "R529") (pin "2") (pinfunction "2_2") (pintype "passive"))
      (node (ref "T500") (pin "2") (pinfunction "Pri-_2") (pintype "passive"))
      (node (ref "U502") (pin "6") (pinfunction "GND_6") (pintype "passive"))
      (node (ref "U503") (pin "3") (pinfunction "4_3") (pintype "passive"))
    )
    (net (code "36") (name "Net-(T500-Sec1+)") (class "Default")
      (node (ref "C520") (pin "2") (pinfunction "2_2") (pintype "passive"))
      (node (ref "C521") (pin "2") (pinfunction "2_2") (pintype "passive"))
      (node (ref "F1") (pin "2") (pinfunction "2_2") (pintype "passive"))
      (node (ref "JP500") (pin "1") (pinfunction "1_1") (pintype "passive"))
      (node (ref "JP500") (pin "2") (pinfunction "2_2") (pintype "passive"))
      (node (ref "R525") (pin "2") (pinfunction "2_2") (pintype "passive"))
      (node (ref "T500") (pin "3") (pinfunction "Sec1+_3") (pintype "passive"))
    )
    (net (code "37") (name "Net-(U500-A)") (class "Default")
      (node (ref "JP502") (pin "3") (pinfunction "3_3") (pintype "passive"))
      (node (ref "U500") (pin "12") (pinfunction "A_12") (pintype "passive"))
    )
    (net (code "38") (name "Net-(U500-B)") (class "Default")
      (node (ref "JP502") (pin "4") (pinfunction "4_4") (pintype "passive"))
      (node (ref "U500") (pin "13") (pinfunction "B_13") (pintype "passive"))
    )
    (net (code "39") (name "Net-(U500-DE)") (class "Default")
      (node (ref "C526") (pin "2") (pinfunction "2_2") (pintype "passive"))
      (node (ref "U500") (pin "5") (pinfunction "DE_5") (pintype "passive"))
      (node (ref "X506") (pin "1") (pinfunction "1_1") (pintype "passive"))
    )
    (net (code "40") (name "Net-(U500-PV)") (class "Default")
      (node (ref "C27") (pin "1") (pinfunction "1_1") (pintype "passive"))
      (node (ref "JP501") (pin "5") (pinfunction "5_5") (pintype "passive"))
      (node (ref "L501") (pin "1") (pinfunction "1_1") (pintype "passive"))
      (node (ref "R507") (pin "1") (pinfunction "1_1") (pintype "passive"))
      (node (ref "U500") (pin "1") (pinfunction "Vcc1_1") (pintype "passive"))
      (node (ref "U500") (pin "7") (pinfunction "PV_7") (pintype "passive"))
      (node (ref "U504") (pin "3") (pinfunction "IN_3") (pintype "power_in"))
      (node (ref "U505") (pin "1") (pinfunction "Vcc1_1") (pintype "passive"))
      (node (ref "U505") (pin "7") (pinfunction "PV_7") (pintype "passive"))
    )
    (net (code "41") (name "Net-(U500-RXD)") (class "Default")
      (node (ref "U500") (pin "3") (pinfunction "RXD_3") (pintype "passive"))
      (node (ref "X504") (pin "1") (pinfunction "1_1") (pintype "passive"))
    )
    (net (code "42") (name "Net-(U500-TXD)") (class "Default")
      (node (ref "U500") (pin "6") (pinfunction "TXD_6") (pintype "passive"))
      (node (ref "X505") (pin "1") (pinfunction "1_1") (pintype "passive"))
    )
    (net (code "43") (name "Net-(U500-Vcc2)") (class "Default")
      (node (ref "C531") (pin "2") (pinfunction "2_2") (pintype "passive"))
      (node (ref "U500") (pin "16") (pinfunction "Vcc2_16") (pintype "passive"))
      (node (ref "U507") (pin "2") (pinfunction "OUT_2") (pintype "power_in"))
      (node (ref "U507") (pin "4") (pinfunction "OUT_4") (pintype "power_in"))
    )
    (net (code "44") (name "Net-(U501-OUT)") (class "Default")
      (node (ref "C507") (pin "2") (pinfunction "2_2") (pintype "passive"))
      (node (ref "JP501") (pin "8") (pinfunction "8_8") (pintype "passive"))
      (node (ref "U501") (pin "1") (pinfunction "OUT_1") (pintype "power_in"))
    )
    (net (code "45") (name "Net-(U502-COMP)") (class "Default")
      (node (ref "C513") (pin "2") (pinfunction "2_2") (pintype "passive"))
      (node (ref "C516") (pin "2") (pinfunction "2_2") (pintype "passive"))
      (node (ref "R513") (pin "1") (pinfunction "1_1") (pintype "passive"))
      (node (ref "U502") (pin "2") (pinfunction "COMP_2") (pintype "passive"))
      (node (ref "U503") (pin "4") (pinfunction "2_4") (pintype "passive"))
    )
    (net (code "46") (name "Net-(U502-CS)") (class "Default")
      (node (ref "C515") (pin "1") (pinfunction "1_1") (pintype "passive"))
      (node (ref "R523") (pin "2") (pinfunction "2_2") (pintype "passive"))
      (node (ref "U502") (pin "4") (pinfunction "CS_4") (pintype "passive"))
    )
    (net (code "47") (name "Net-(U502-GD)") (class "Default")
      (node (ref "R522") (pin "2") (pinfunction "2_2") (pintype "passive"))
      (node (ref "U502") (pin "7") (pinfunction "GD_7") (pintype "passive"))
    )
    (net (code "48") (name "Net-(U502-INV)") (class "Default")
      (node (ref "C513") (pin "1") (pinfunction "1_1") (pintype "passive"))
      (node (ref "R502") (pin "1") (pinfunction "1_1") (pintype "passive"))
      (node (ref "R506") (pin "2") (pinfunction "2_2") (pintype "passive"))
      (node (ref "R513") (pin "2") (pinfunction "2_2") (pintype "passive"))
      (node (ref "U502") (pin "1") (pinfunction "INV_1") (pintype "passive"))
    )
    (net (code "49") (name "Net-(U502-UFF)") (class "Default")
      (node (ref "C514") (pin "1") (pinfunction "1_1") (pintype "passive"))
      (node (ref "R500") (pin "1") (pinfunction "1_1") (pintype "passive"))
      (node (ref "R524") (pin "2") (pinfunction "2_2") (pintype "passive"))
      (node (ref "U502") (pin "3") (pinfunction "UFF_3") (pintype "passive"))
    )
    (net (code "50") (name "Net-(U502-ZCD)") (class "Default")
      (node (ref "R521") (pin "2") (pinfunction "2_2") (pintype "passive"))
      (node (ref "U502") (pin "5") (pinfunction "ZCD_5") (pintype "passive"))
    )
    (net (code "51") (name "Net-(U503-1)") (class "Default")
      (node (ref "R530") (pin "2") (pinfunction "2_2") (pintype "passive"))
      (node (ref "U503") (pin "2") (pinfunction "1_2") (pintype "passive"))
    )
    (net (code "52") (name "Net-(U505-A)") (class "Default")
      (node (ref "JP502") (pin "1") (pinfunction "1_1") (pintype "passive"))
      (node (ref "U505") (pin "12") (pinfunction "A_12") (pintype "passive"))
    )
    (net (code "53") (name "Net-(U505-B)") (class "Default")
      (node (ref "JP502") (pin "2") (pinfunction "2_2") (pintype "passive"))
      (node (ref "U505") (pin "13") (pinfunction "B_13") (pintype "passive"))
    )
    (net (code "54") (name "Net-(U505-DE)") (class "Default")
      (node (ref "C518") (pin "2") (pinfunction "2_2") (pintype "passive"))
      (node (ref "JP501") (pin "4") (pinfunction "4_4") (pintype "passive"))
      (node (ref "U505") (pin "5") (pinfunction "DE_5") (pintype "passive"))
    )
    (net (code "55") (name "Net-(U505-RXD)") (class "Default")
      (node (ref "JP501") (pin "9") (pinfunction "9_9") (pintype "passive"))
      (node (ref "U505") (pin "3") (pinfunction "RXD_3") (pintype "passive"))
    )
    (net (code "56") (name "Net-(U505-TXD)") (class "Default")
      (node (ref "JP501") (pin "10") (pinfunction "10_10") (pintype "passive"))
      (node (ref "U505") (pin "6") (pinfunction "TXD_6") (pintype "passive"))
    )
    (net (code "57") (name "Net-(U505-Vcc2)") (class "Default")
      (node (ref "C528") (pin "2") (pinfunction "2_2") (pintype "passive"))
      (node (ref "U505") (pin "16") (pinfunction "Vcc2_16") (pintype "passive"))
      (node (ref "U506") (pin "2") (pinfunction "OUT_2") (pintype "power_in"))
      (node (ref "U506") (pin "4") (pinfunction "OUT_4") (pintype "power_in"))
    )
    (net (code "58") (name "Net-(U506-GND)") (class "Default")
      (node (ref "C519") (pin "1") (pinfunction "1_1") (pintype "passive"))
      (node (ref "C527") (pin "1") (pinfunction "1_1") (pintype "passive"))
      (node (ref "C528") (pin "1") (pinfunction "1_1") (pintype "passive"))
      (node (ref "U505") (pin "15") (pinfunction "Vdd2_15") (pintype "passive"))
      (node (ref "U505") (pin "9") (pinfunction "Vdd2_9") (pintype "passive"))
      (node (ref "U506") (pin "1") (pinfunction "GND_1") (pintype "power_in"))
      (node (ref "X501") (pin "1") (pinfunction "1_1") (pintype "passive"))
    )
    (net (code "59") (name "Net-(U507-GND)") (class "Default")
      (node (ref "C529") (pin "1") (pinfunction "1_1") (pintype "passive"))
      (node (ref "C530") (pin "1") (pinfunction "1_1") (pintype "passive"))
      (node (ref "C531") (pin "1") (pinfunction "1_1") (pintype "passive"))
      (node (ref "U500") (pin "15") (pinfunction "Vdd2_15") (pintype "passive"))
      (node (ref "U500") (pin "9") (pinfunction "Vdd2_9") (pintype "passive"))
      (node (ref "U507") (pin "1") (pinfunction "GND_1") (pintype "power_in"))
      (node (ref "X503") (pin "1") (pinfunction "1_1") (pintype "passive"))
    )
    (net (code "60") (name "unconnected-(D511-NC-Pad4)") (class "Default")
      (node (ref "D511") (pin "4") (pinfunction "NC_4") (pintype "passive"))
    )
    (net (code "61") (name "unconnected-(D511-NC-Pad5)") (class "Default")
      (node (ref "D511") (pin "5") (pinfunction "NC_5") (pintype "passive"))
    )
    (net (code "62") (name "unconnected-(JP500-Pad3)") (class "Default")
      (node (ref "JP500") (pin "3") (pinfunction "3_3") (pintype "passive"))
    )
    (net (code "63") (name "unconnected-(JP500-Pad4)") (class "Default")
      (node (ref "JP500") (pin "4") (pinfunction "4_4") (pintype "passive"))
    )
    (net (code "64") (name "unconnected-(JP500-Pad5)") (class "Default")
      (node (ref "JP500") (pin "5") (pinfunction "5_5") (pintype "passive"))
    )
    (net (code "65") (name "unconnected-(JP500-Pad6)") (class "Default")
      (node (ref "JP500") (pin "6") (pinfunction "6_6") (pintype "passive"))
    )
    (net (code "66") (name "unconnected-(JP500-Pad7)") (class "Default")
      (node (ref "JP500") (pin "7") (pinfunction "7_7") (pintype "passive"))
    )
    (net (code "67") (name "unconnected-(JP500-Pad8)") (class "Default")
      (node (ref "JP500") (pin "8") (pinfunction "8_8") (pintype "passive"))
    )
    (net (code "68") (name "unconnected-(L500-Pad9)") (class "Default")
      (node (ref "L500") (pin "9") (pintype "passive"))
    )
    (net (code "69") (name "unconnected-(L500-Pad10)") (class "Default")
      (node (ref "L500") (pin "10") (pinfunction "10_10") (pintype "passive"))
    )
    (net (code "70") (name "unconnected-(U501-NC-Pad4)") (class "Default")
      (node (ref "U501") (pin "4") (pinfunction "NC_4") (pintype "passive"))
    )
    (net (code "71") (name "unconnected-(U501-NC-Pad8)") (class "Default")
      (node (ref "U501") (pin "8") (pinfunction "NC_8") (pintype "passive"))
    )
    (net (code "72") (name "unconnected-(X507-Pad1)") (class "Default")
      (node (ref "X507") (pin "1") (pinfunction "1_1") (pintype "passive"))
    )
  )
)
